# debounce_rev_2.net
KiCad netlist of a schematic drawn in EAGLE
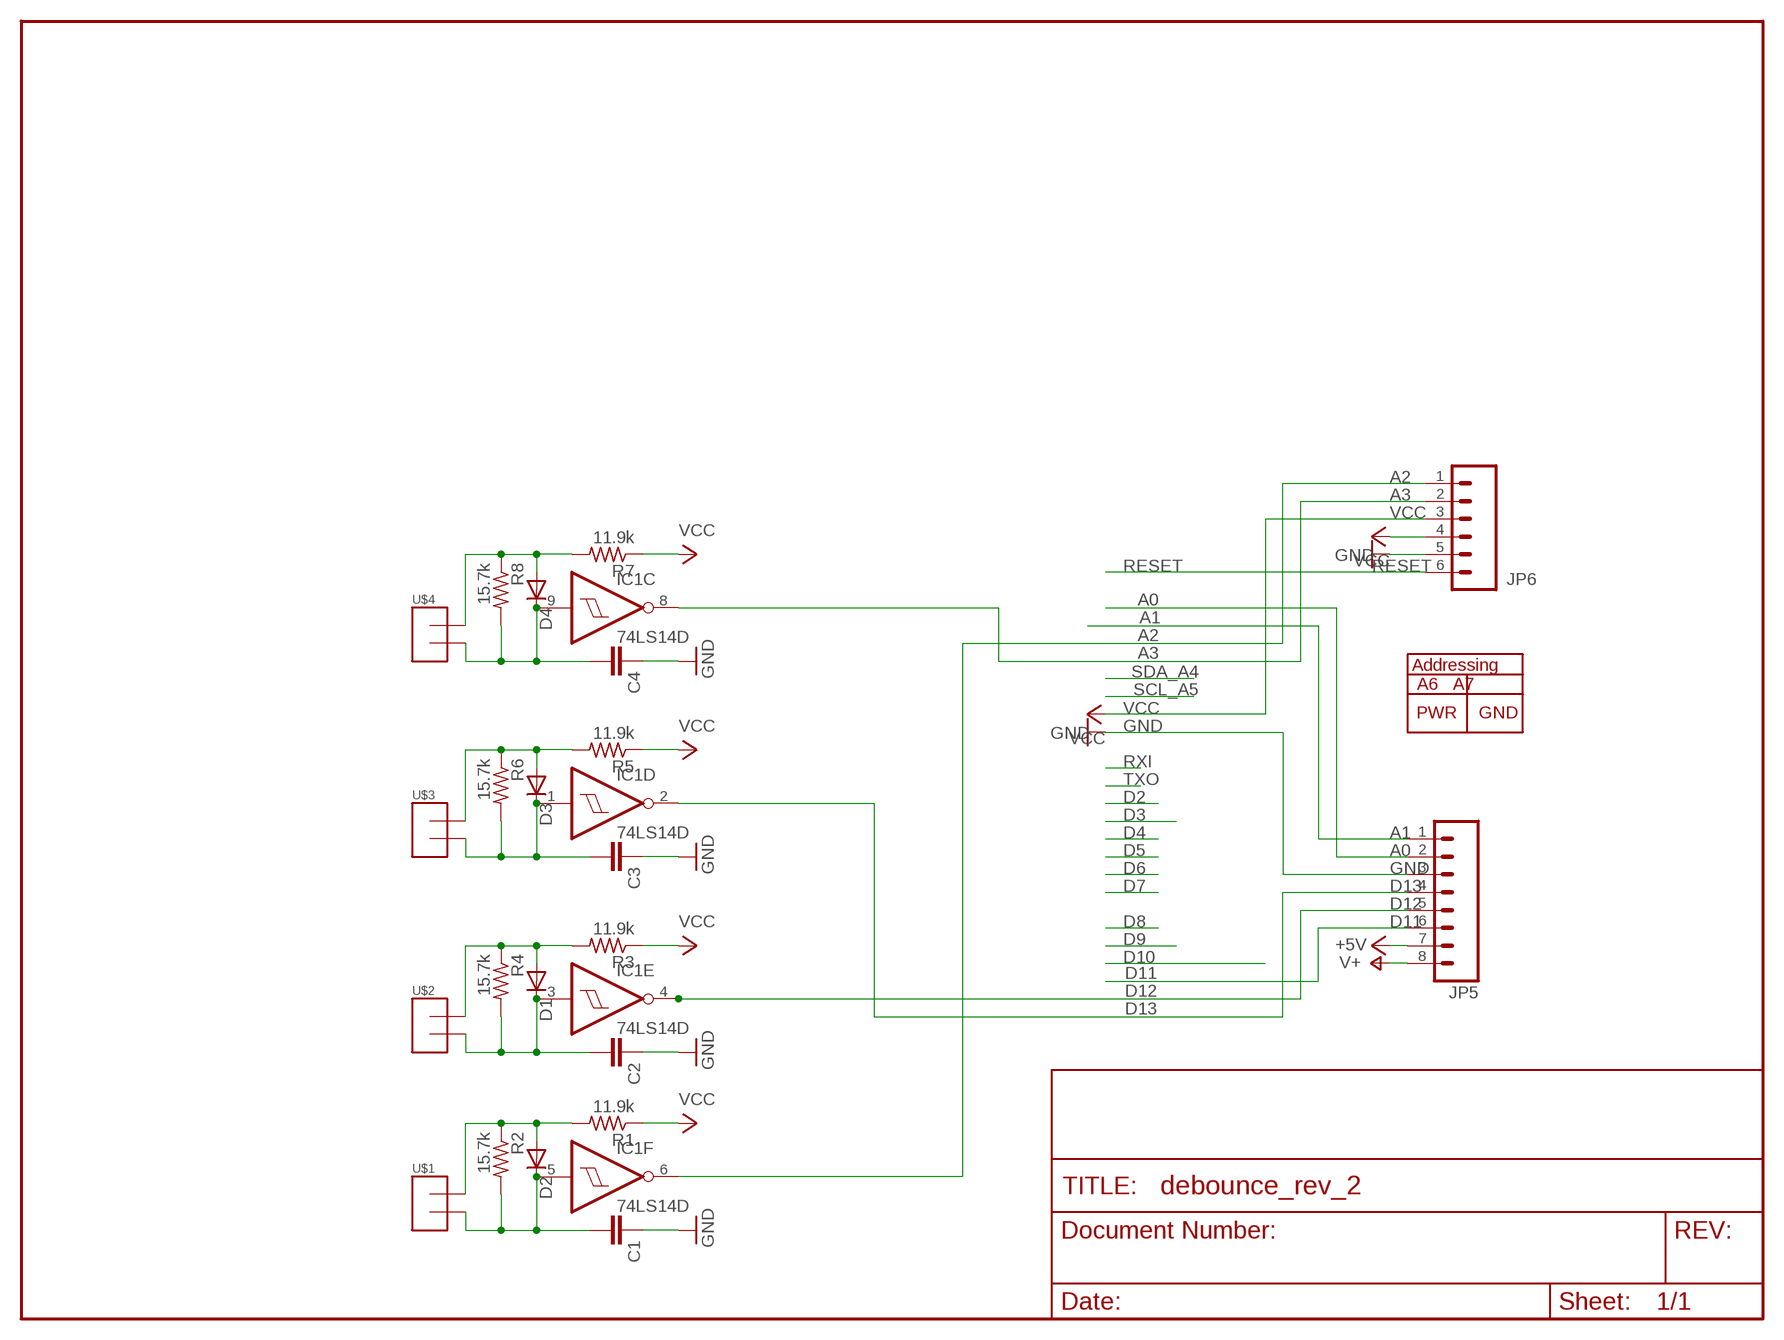
[diagram p0: schematic, sheet 1]

(export (version "E")
  (design (tool "Eeschema 10.0.6"))
  (components
    (comp (ref "C1")
      (value "CAPPTH")
      (footprint "eagle-import:CAP-PTH-SMALL")
      (libsource (lib "eagle-import") (part "CAPPTH"))
    )
    (comp (ref "C2")
      (value "CAPPTH")
      (footprint "eagle-import:CAP-PTH-SMALL")
      (libsource (lib "eagle-import") (part "CAPPTH"))
    )
    (comp (ref "C3")
      (value "CAPPTH")
      (footprint "eagle-import:CAP-PTH-SMALL")
      (libsource (lib "eagle-import") (part "CAPPTH"))
    )
    (comp (ref "C4")
      (value "CAPPTH")
      (footprint "eagle-import:CAP-PTH-SMALL")
      (libsource (lib "eagle-import") (part "CAPPTH"))
    )
    (comp (ref "D1")
      (value "DIODE-D-2.5")
      (footprint "eagle-import:D-2.5")
      (libsource (lib "eagle-import") (part "DIODE-D-2.5"))
    )
    (comp (ref "D2")
      (value "DIODE-D-2.5")
      (footprint "eagle-import:D-2.5")
      (libsource (lib "eagle-import") (part "DIODE-D-2.5"))
    )
    (comp (ref "D3")
      (value "DIODE-D-2.5")
      (footprint "eagle-import:D-2.5")
      (libsource (lib "eagle-import") (part "DIODE-D-2.5"))
    )
    (comp (ref "D4")
      (value "DIODE-D-2.5")
      (footprint "eagle-import:D-2.5")
      (libsource (lib "eagle-import") (part "DIODE-D-2.5"))
    )
    (comp (ref "IC1")
      (value "74LS14D")
      (footprint "eagle-import:SO14")
      (libsource (lib "eagle-import") (part "7414DLS"))
    )
    (comp (ref "JP5")
      (value "M081X08")
      (footprint "eagle-import:1X08")
      (libsource (lib "eagle-import") (part "M081X08"))
    )
    (comp (ref "JP6")
      (value "M06SIP")
      (footprint "eagle-import:1X06")
      (libsource (lib "eagle-import") (part "M06SIP"))
    )
    (comp (ref "R1")
      (value "11.9k")
      (footprint "eagle-import:0204V")
      (libsource (lib "eagle-import") (part "R-US_0204/2V"))
    )
    (comp (ref "R2")
      (value "15.7k")
      (footprint "eagle-import:0204V")
      (libsource (lib "eagle-import") (part "R-US_0204/2V"))
    )
    (comp (ref "R3")
      (value "11.9k")
      (footprint "eagle-import:0204V")
      (libsource (lib "eagle-import") (part "R-US_0204/2V"))
    )
    (comp (ref "R4")
      (value "15.7k")
      (footprint "eagle-import:0204V")
      (libsource (lib "eagle-import") (part "R-US_0204/2V"))
    )
    (comp (ref "R5")
      (value "11.9k")
      (footprint "eagle-import:0204V")
      (libsource (lib "eagle-import") (part "R-US_0204/2V"))
    )
    (comp (ref "R6")
      (value "15.7k")
      (footprint "eagle-import:0204V")
      (libsource (lib "eagle-import") (part "R-US_0204/2V"))
    )
    (comp (ref "R7")
      (value "11.9k")
      (footprint "eagle-import:0204V")
      (libsource (lib "eagle-import") (part "R-US_0204/2V"))
    )
    (comp (ref "R8")
      (value "15.7k")
      (footprint "eagle-import:0204V")
      (libsource (lib "eagle-import") (part "R-US_0204/2V"))
    )
    (comp (ref "U$1")
      (value "TERMINAL2")
      (footprint "eagle-import:TERMINAL_2")
      (libsource (lib "eagle-import") (part "TERMINAL2"))
    )
    (comp (ref "U$2")
      (value "TERMINAL2")
      (footprint "eagle-import:TERMINAL_2")
      (libsource (lib "eagle-import") (part "TERMINAL2"))
    )
    (comp (ref "U$3")
      (value "TERMINAL2")
      (footprint "eagle-import:TERMINAL_2")
      (libsource (lib "eagle-import") (part "TERMINAL2"))
    )
    (comp (ref "U$4")
      (value "TERMINAL2")
      (footprint "eagle-import:TERMINAL_2")
      (libsource (lib "eagle-import") (part "TERMINAL2"))
    )
  )
  (nets
    (net (code "1") (name "+5V") (class "Default")
      (node (ref "JP5") (pin "7") (pinfunction "7_7") (pintype "passive"))
    )
    (net (code "2") (name "/A0") (class "Default")
      (node (ref "JP5") (pin "2") (pinfunction "2_2") (pintype "passive"))
    )
    (net (code "3") (name "/A1") (class "Default")
      (node (ref "JP5") (pin "1") (pinfunction "1_1") (pintype "passive"))
    )
    (net (code "4") (name "/A2") (class "Default")
      (node (ref "IC1") (pin "6") (pinfunction "O_6") (pintype "output"))
      (node (ref "JP6") (pin "1") (pinfunction "1_1") (pintype "passive"))
    )
    (net (code "5") (name "/A3") (class "Default")
      (node (ref "IC1") (pin "8") (pinfunction "O_8") (pintype "output"))
      (node (ref "JP6") (pin "2") (pinfunction "2_2") (pintype "passive"))
    )
    (net (code "15") (name "/D11") (class "Default")
      (node (ref "JP5") (pin "6") (pinfunction "6_6") (pintype "passive"))
    )
    (net (code "16") (name "/D12") (class "Default")
      (node (ref "IC1") (pin "4") (pinfunction "O_4") (pintype "output"))
      (node (ref "JP5") (pin "5") (pinfunction "5_5") (pintype "passive"))
    )
    (net (code "17") (name "/D13") (class "Default")
      (node (ref "IC1") (pin "2") (pinfunction "O_2") (pintype "output"))
      (node (ref "JP5") (pin "4") (pinfunction "4_4") (pintype "passive"))
    )
    (net (code "18") (name "/RESET") (class "Default")
      (node (ref "JP6") (pin "6") (pinfunction "6_6") (pintype "passive"))
    )
    (net (code "23") (name "GND") (class "Default")
      (node (ref "C1") (pin "1") (pinfunction "1_1") (pintype "passive"))
      (node (ref "C2") (pin "1") (pinfunction "1_1") (pintype "passive"))
      (node (ref "C3") (pin "1") (pinfunction "1_1") (pintype "passive"))
      (node (ref "C4") (pin "1") (pinfunction "1_1") (pintype "passive"))
      (node (ref "JP5") (pin "3") (pinfunction "3_3") (pintype "passive"))
      (node (ref "JP6") (pin "5") (pinfunction "5_5") (pintype "passive"))
    )
    (net (code "24") (name "Net-(D1-PadA)") (class "Default")
      (node (ref "D1") (pin "A") (pinfunction "A_A") (pintype "passive"))
      (node (ref "R3") (pin "2") (pinfunction "2_2") (pintype "passive"))
      (node (ref "R4") (pin "1") (pinfunction "1_1") (pintype "passive"))
      (node (ref "U$2") (pin "P$1") (pinfunction "P$1_P$1") (pintype "bidirectional"))
    )
    (net (code "25") (name "Net-(D2-PadA)") (class "Default")
      (node (ref "D2") (pin "A") (pinfunction "A_A") (pintype "passive"))
      (node (ref "R1") (pin "2") (pinfunction "2_2") (pintype "passive"))
      (node (ref "R2") (pin "1") (pinfunction "1_1") (pintype "passive"))
      (node (ref "U$1") (pin "P$1") (pinfunction "P$1_P$1") (pintype "bidirectional"))
    )
    (net (code "26") (name "Net-(D3-PadA)") (class "Default")
      (node (ref "D3") (pin "A") (pinfunction "A_A") (pintype "passive"))
      (node (ref "R5") (pin "2") (pinfunction "2_2") (pintype "passive"))
      (node (ref "R6") (pin "1") (pinfunction "1_1") (pintype "passive"))
      (node (ref "U$3") (pin "P$1") (pinfunction "P$1_P$1") (pintype "bidirectional"))
    )
    (net (code "27") (name "Net-(D4-PadA)") (class "Default")
      (node (ref "D4") (pin "A") (pinfunction "A_A") (pintype "passive"))
      (node (ref "R7") (pin "2") (pinfunction "2_2") (pintype "passive"))
      (node (ref "R8") (pin "1") (pinfunction "1_1") (pintype "passive"))
      (node (ref "U$4") (pin "P$1") (pinfunction "P$1_P$1") (pintype "bidirectional"))
    )
    (net (code "28") (name "Net-(IC1C-I)") (class "Default")
      (node (ref "C4") (pin "2") (pinfunction "2_2") (pintype "passive"))
      (node (ref "D4") (pin "C") (pinfunction "C_C") (pintype "passive"))
      (node (ref "IC1") (pin "9") (pinfunction "I_9") (pintype "input"))
      (node (ref "R8") (pin "2") (pinfunction "2_2") (pintype "passive"))
      (node (ref "U$4") (pin "P$2") (pinfunction "P$2_P$2") (pintype "bidirectional"))
    )
    (net (code "29") (name "Net-(IC1D-I)") (class "Default")
      (node (ref "C3") (pin "2") (pinfunction "2_2") (pintype "passive"))
      (node (ref "D3") (pin "C") (pinfunction "C_C") (pintype "passive"))
      (node (ref "IC1") (pin "1") (pinfunction "I_1") (pintype "input"))
      (node (ref "R6") (pin "2") (pinfunction "2_2") (pintype "passive"))
      (node (ref "U$3") (pin "P$2") (pinfunction "P$2_P$2") (pintype "bidirectional"))
    )
    (net (code "30") (name "Net-(IC1E-I)") (class "Default")
      (node (ref "C2") (pin "2") (pinfunction "2_2") (pintype "passive"))
      (node (ref "D1") (pin "C") (pinfunction "C_C") (pintype "passive"))
      (node (ref "IC1") (pin "3") (pinfunction "I_3") (pintype "input"))
      (node (ref "R4") (pin "2") (pinfunction "2_2") (pintype "passive"))
      (node (ref "U$2") (pin "P$2") (pinfunction "P$2_P$2") (pintype "bidirectional"))
    )
    (net (code "31") (name "Net-(IC1F-I)") (class "Default")
      (node (ref "C1") (pin "2") (pinfunction "2_2") (pintype "passive"))
      (node (ref "D2") (pin "C") (pinfunction "C_C") (pintype "passive"))
      (node (ref "IC1") (pin "5") (pinfunction "I_5") (pintype "input"))
      (node (ref "R2") (pin "2") (pinfunction "2_2") (pintype "passive"))
      (node (ref "U$1") (pin "P$2") (pinfunction "P$2_P$2") (pintype "bidirectional"))
    )
    (net (code "32") (name "V+") (class "Default")
      (node (ref "JP5") (pin "8") (pinfunction "8_8") (pintype "passive"))
    )
    (net (code "33") (name "VCC") (class "Default")
      (node (ref "JP6") (pin "3") (pinfunction "3_3") (pintype "passive"))
      (node (ref "JP6") (pin "4") (pinfunction "4_4") (pintype "passive"))
      (node (ref "R1") (pin "1") (pinfunction "1_1") (pintype "passive"))
      (node (ref "R3") (pin "1") (pinfunction "1_1") (pintype "passive"))
      (node (ref "R5") (pin "1") (pinfunction "1_1") (pintype "passive"))
      (node (ref "R7") (pin "1") (pinfunction "1_1") (pintype "passive"))
    )
  )
)
